# untitled.net
KiCad netlist of a schematic drawn in EAGLE
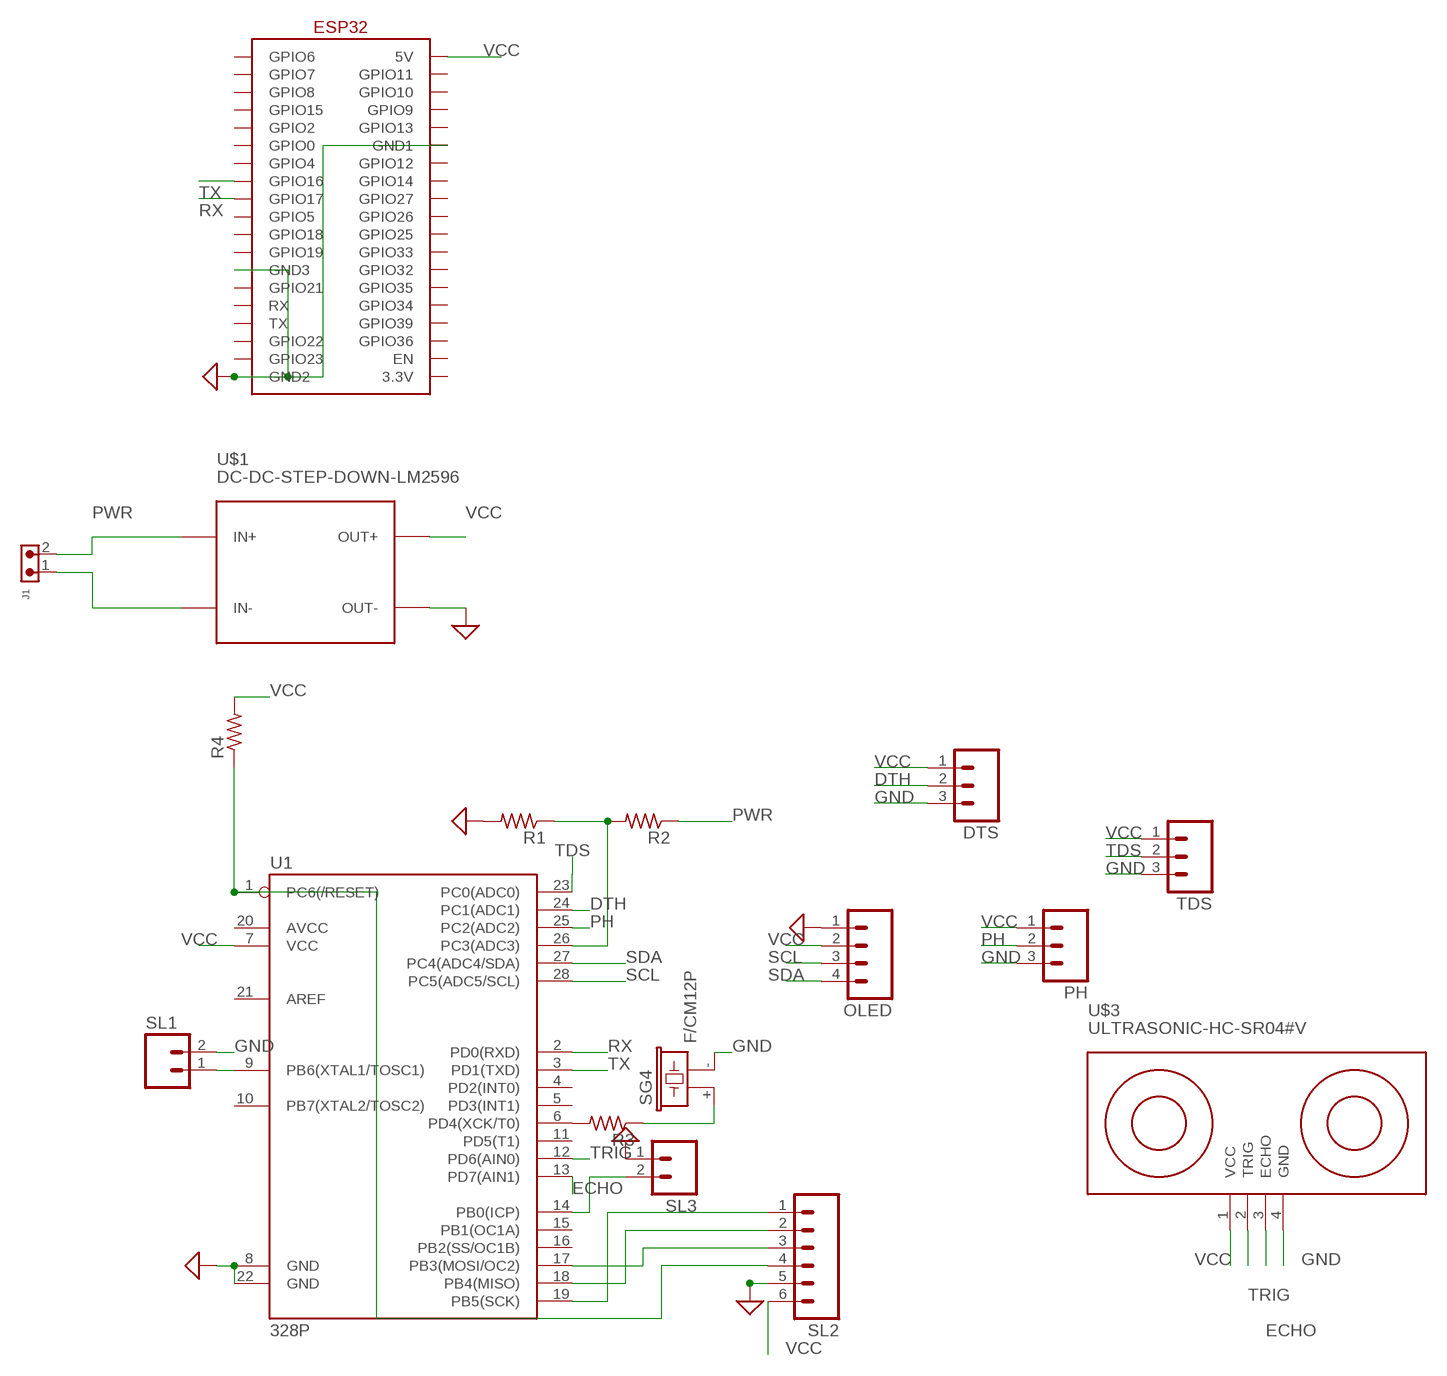
[diagram p0: schematic, sheet 1]

(export (version "E")
  (design (tool "Eeschema 10.0.6"))
  (components
    (comp (ref "DTS")
      (value "M03")
      (footprint "eagle-import:03P")
      (libsource (lib "eagle-import") (part "M03"))
    )
    (comp (ref "J1")
      (value "691305530002")
      (footprint "eagle-import:691305530002")
      (libsource (lib "eagle-import") (part "691305530002"))
    )
    (comp (ref "OLED")
      (value "M04")
      (footprint "eagle-import:04P")
      (libsource (lib "eagle-import") (part "M04"))
    )
    (comp (ref "PH")
      (value "M03")
      (footprint "eagle-import:03P")
      (libsource (lib "eagle-import") (part "M03"))
    )
    (comp (ref "R1")
      (value "R-US_0207/10")
      (footprint "eagle-import:0207_10")
      (libsource (lib "eagle-import") (part "R-US_0207/10"))
    )
    (comp (ref "R2")
      (value "R-US_0207/10")
      (footprint "eagle-import:0207_10")
      (libsource (lib "eagle-import") (part "R-US_0207/10"))
    )
    (comp (ref "R3")
      (value "R-US_0204/2V")
      (footprint "eagle-import:0204V")
      (libsource (lib "eagle-import") (part "R-US_0204/2V"))
    )
    (comp (ref "R4")
      (value "R-US_0207/10")
      (footprint "eagle-import:0207_10")
      (libsource (lib "eagle-import") (part "R-US_0207/10"))
    )
    (comp (ref "SG4")
      (value "F/CM12P")
      (footprint "eagle-import:F_CM12P")
      (libsource (lib "eagle-import") (part "F/CM12P"))
    )
    (comp (ref "SL1")
      (value "M02")
      (footprint "eagle-import:02P")
      (libsource (lib "eagle-import") (part "M02"))
    )
    (comp (ref "SL2")
      (value "M06")
      (footprint "eagle-import:06P")
      (libsource (lib "eagle-import") (part "M06"))
    )
    (comp (ref "SL3")
      (value "M02")
      (footprint "eagle-import:02P")
      (libsource (lib "eagle-import") (part "M02"))
    )
    (comp (ref "TDS")
      (value "M03")
      (footprint "eagle-import:03P")
      (libsource (lib "eagle-import") (part "M03"))
    )
    (comp (ref "U$1")
      (value "DC-DC-STEP-DOWN-LM2596")
      (footprint "eagle-import:DC-DC-STEP-DOWN-LM2596")
      (libsource (lib "eagle-import") (part "DC-DC-STEP-DOWN-LM2596"))
    )
    (comp (ref "U$2")
      (value "ESP32")
      (footprint "eagle-import:ESP32")
      (libsource (lib "eagle-import") (part "ESP32"))
    )
    (comp (ref "U$3")
      (value "ULTRASONIC-HC-SR04#V")
      (footprint "eagle-import:ULTRASONIC-HC-SR04#V")
      (libsource (lib "eagle-import") (part "ULTRASONIC-HC-SR04#V"))
    )
    (comp (ref "U1")
      (value "328P")
      (footprint "eagle-import:DIP28")
      (libsource (lib "eagle-import") (part "ATMEGA328P_PDIP"))
    )
  )
  (nets
    (net (code "1") (name "/DTH") (class "Default")
      (node (ref "DTS") (pin "2") (pinfunction "2_2") (pintype "passive"))
      (node (ref "U1") (pin "24") (pinfunction "PC1(ADC1)_24") (pintype "bidirectional"))
    )
    (net (code "2") (name "/ECHO") (class "Default")
      (node (ref "U$3") (pin "3") (pinfunction "ECHO_3") (pintype "output"))
      (node (ref "U1") (pin "13") (pinfunction "PD7(AIN1)_13") (pintype "bidirectional"))
    )
    (net (code "3") (name "/PH") (class "Default")
      (node (ref "PH") (pin "2") (pinfunction "2_2") (pintype "passive"))
      (node (ref "U1") (pin "25") (pinfunction "PC2(ADC2)_25") (pintype "bidirectional"))
    )
    (net (code "4") (name "/PWR") (class "Default")
      (node (ref "J1") (pin "2") (pinfunction "2_2") (pintype "passive"))
      (node (ref "R2") (pin "1") (pinfunction "1_1") (pintype "passive"))
      (node (ref "U$1") (pin "IN+") (pinfunction "IN+_IN+") (pintype "bidirectional"))
    )
    (net (code "5") (name "/RX") (class "Default")
      (node (ref "U$2") (pin "GPIO17") (pinfunction "GPIO17_GPIO17") (pintype "bidirectional"))
      (node (ref "U1") (pin "2") (pinfunction "PD0(RXD)_2") (pintype "bidirectional"))
    )
    (net (code "6") (name "/SCL") (class "Default")
      (node (ref "OLED") (pin "3") (pinfunction "3_3") (pintype "passive"))
      (node (ref "U1") (pin "28") (pinfunction "PC5(ADC5/SCL)_28") (pintype "bidirectional"))
    )
    (net (code "7") (name "/SDA") (class "Default")
      (node (ref "OLED") (pin "4") (pinfunction "4_4") (pintype "passive"))
      (node (ref "U1") (pin "27") (pinfunction "PC4(ADC4/SDA)_27") (pintype "bidirectional"))
    )
    (net (code "8") (name "/TDS") (class "Default")
      (node (ref "TDS") (pin "2") (pinfunction "2_2") (pintype "passive"))
      (node (ref "U1") (pin "23") (pinfunction "PC0(ADC0)_23") (pintype "bidirectional"))
    )
    (net (code "9") (name "/TRIG") (class "Default")
      (node (ref "U$3") (pin "2") (pinfunction "TRIG_2") (pintype "input"))
      (node (ref "U1") (pin "12") (pinfunction "PD6(AIN0)_12") (pintype "bidirectional"))
    )
    (net (code "10") (name "/TX") (class "Default")
      (node (ref "U$2") (pin "GPIO16") (pinfunction "GPIO16_GPIO16") (pintype "bidirectional"))
      (node (ref "U1") (pin "3") (pinfunction "PD1(TXD)_3") (pintype "bidirectional"))
    )
    (net (code "11") (name "/VCC") (class "Default")
      (node (ref "DTS") (pin "1") (pinfunction "1_1") (pintype "passive"))
      (node (ref "OLED") (pin "2") (pinfunction "2_2") (pintype "passive"))
      (node (ref "PH") (pin "1") (pinfunction "1_1") (pintype "passive"))
      (node (ref "R4") (pin "2") (pinfunction "2_2") (pintype "passive"))
      (node (ref "SL2") (pin "6") (pinfunction "6_6") (pintype "passive"))
      (node (ref "TDS") (pin "1") (pinfunction "1_1") (pintype "passive"))
      (node (ref "U$1") (pin "OUT+") (pinfunction "OUT+_OUT+") (pintype "bidirectional"))
      (node (ref "U$2") (pin "5V") (pinfunction "5V_5V") (pintype "bidirectional"))
      (node (ref "U$3") (pin "1") (pinfunction "VCC_1") (pintype "power_in"))
      (node (ref "U1") (pin "7") (pinfunction "VCC_7") (pintype "bidirectional"))
    )
    (net (code "12") (name "Net-(J1-Pad1)") (class "Default")
      (node (ref "J1") (pin "1") (pinfunction "1_1") (pintype "passive"))
      (node (ref "U$1") (pin "IN-") (pinfunction "IN-_IN-") (pintype "bidirectional"))
    )
    (net (code "13") (name "Net-(SG4-1)") (class "Default")
      (node (ref "R3") (pin "1") (pinfunction "1_1") (pintype "passive"))
      (node (ref "SG4") (pin "+") (pinfunction "1_+") (pintype "passive"))
    )
    (net (code "14") (name "Net-(U1-PB0(ICP))") (class "Default")
      (node (ref "SL3") (pin "2") (pinfunction "2_2") (pintype "passive"))
      (node (ref "U1") (pin "14") (pinfunction "PB0(ICP)_14") (pintype "bidirectional"))
    )
    (net (code "15") (name "Net-(U1-PB3(MOSI{slash}OC2))") (class "Default")
      (node (ref "SL2") (pin "3") (pinfunction "3_3") (pintype "passive"))
      (node (ref "U1") (pin "17") (pinfunction "PB3(MOSI/OC2)_17") (pintype "bidirectional"))
    )
    (net (code "16") (name "Net-(U1-PB4(MISO))") (class "Default")
      (node (ref "SL2") (pin "2") (pinfunction "2_2") (pintype "passive"))
      (node (ref "U1") (pin "18") (pinfunction "PB4(MISO)_18") (pintype "bidirectional"))
    )
    (net (code "17") (name "Net-(U1-PB5(SCK))") (class "Default")
      (node (ref "SL2") (pin "1") (pinfunction "1_1") (pintype "passive"))
      (node (ref "U1") (pin "19") (pinfunction "PB5(SCK)_19") (pintype "bidirectional"))
    )
    (net (code "18") (name "Net-(U1-PB6(XTAL1{slash}TOSC1))") (class "Default")
      (node (ref "SL1") (pin "1") (pinfunction "1_1") (pintype "passive"))
      (node (ref "U1") (pin "9") (pinfunction "PB6(XTAL1/TOSC1)_9") (pintype "bidirectional"))
    )
    (net (code "19") (name "Net-(U1-PC3(ADC3))") (class "Default")
      (node (ref "R1") (pin "1") (pinfunction "1_1") (pintype "passive"))
      (node (ref "R2") (pin "2") (pinfunction "2_2") (pintype "passive"))
      (node (ref "U1") (pin "26") (pinfunction "PC3(ADC3)_26") (pintype "bidirectional"))
    )
    (net (code "20") (name "Net-(U1-PC6({slash}RESET))") (class "Default")
      (node (ref "R4") (pin "1") (pinfunction "1_1") (pintype "passive"))
      (node (ref "SL2") (pin "4") (pinfunction "4_4") (pintype "passive"))
      (node (ref "U1") (pin "1") (pinfunction "PC6(/RESET)_1") (pintype "bidirectional"))
    )
    (net (code "21") (name "Net-(U1-PD4(XCK{slash}T0))") (class "Default")
      (node (ref "R3") (pin "2") (pinfunction "2_2") (pintype "passive"))
      (node (ref "U1") (pin "6") (pinfunction "PD4(XCK/T0)_6") (pintype "bidirectional"))
    )
    (net (code "22") (name "SUP") (class "Default")
      (node (ref "DTS") (pin "3") (pinfunction "3_3") (pintype "passive"))
      (node (ref "OLED") (pin "1") (pinfunction "1_1") (pintype "passive"))
      (node (ref "PH") (pin "3") (pinfunction "3_3") (pintype "passive"))
      (node (ref "R1") (pin "2") (pinfunction "2_2") (pintype "passive"))
      (node (ref "SG4") (pin "-") (pinfunction "2_-") (pintype "passive"))
      (node (ref "SL1") (pin "2") (pinfunction "2_2") (pintype "passive"))
      (node (ref "SL2") (pin "5") (pinfunction "5_5") (pintype "passive"))
      (node (ref "SL3") (pin "1") (pinfunction "1_1") (pintype "passive"))
      (node (ref "TDS") (pin "3") (pinfunction "3_3") (pintype "passive"))
      (node (ref "U$1") (pin "OUT-") (pinfunction "OUT-_OUT-") (pintype "bidirectional"))
      (node (ref "U$2") (pin "GND1") (pinfunction "GND1_GND1") (pintype "bidirectional"))
      (node (ref "U$2") (pin "GND2") (pinfunction "GND2_GND2") (pintype "bidirectional"))
      (node (ref "U$2") (pin "GND3") (pinfunction "GND3_GND3") (pintype "bidirectional"))
      (node (ref "U$3") (pin "4") (pinfunction "GND_4") (pintype "power_in"))
      (node (ref "U1") (pin "22") (pinfunction "GND_22") (pintype "bidirectional"))
      (node (ref "U1") (pin "8") (pinfunction "GND_8") (pintype "bidirectional"))
    )
    (net (code "23") (name "unconnected-(U$2-Pad3.3V)") (class "Default")
      (node (ref "U$2") (pin "3.3V") (pinfunction "3.3V_3.3V") (pintype "bidirectional"))
    )
    (net (code "24") (name "unconnected-(U$2-PadEN)") (class "Default")
      (node (ref "U$2") (pin "EN") (pinfunction "EN_EN") (pintype "bidirectional"))
    )
    (net (code "25") (name "unconnected-(U$2-PadGPIO0)") (class "Default")
      (node (ref "U$2") (pin "GPIO0") (pinfunction "GPIO0_GPIO0") (pintype "bidirectional"))
    )
    (net (code "26") (name "unconnected-(U$2-PadGPIO2)") (class "Default")
      (node (ref "U$2") (pin "GPIO2") (pinfunction "GPIO2_GPIO2") (pintype "bidirectional"))
    )
    (net (code "27") (name "unconnected-(U$2-PadGPIO4)") (class "Default")
      (node (ref "U$2") (pin "GPIO4") (pinfunction "GPIO4_GPIO4") (pintype "bidirectional"))
    )
    (net (code "28") (name "unconnected-(U$2-PadGPIO5)") (class "Default")
      (node (ref "U$2") (pin "GPIO5") (pinfunction "GPIO5_GPIO5") (pintype "bidirectional"))
    )
    (net (code "29") (name "unconnected-(U$2-PadGPIO6)") (class "Default")
      (node (ref "U$2") (pin "GPIO6") (pinfunction "GPIO6_GPIO6") (pintype "bidirectional"))
    )
    (net (code "30") (name "unconnected-(U$2-PadGPIO7)") (class "Default")
      (node (ref "U$2") (pin "GPIO7") (pinfunction "GPIO7_GPIO7") (pintype "bidirectional"))
    )
    (net (code "31") (name "unconnected-(U$2-PadGPIO8)") (class "Default")
      (node (ref "U$2") (pin "GPIO8") (pinfunction "GPIO8_GPIO8") (pintype "bidirectional"))
    )
    (net (code "32") (name "unconnected-(U$2-PadGPIO9)") (class "Default")
      (node (ref "U$2") (pin "GPIO9") (pinfunction "GPIO9_GPIO9") (pintype "bidirectional"))
    )
    (net (code "33") (name "unconnected-(U$2-PadGPIO10)") (class "Default")
      (node (ref "U$2") (pin "GPIO10") (pinfunction "GPIO10_GPIO10") (pintype "bidirectional"))
    )
    (net (code "34") (name "unconnected-(U$2-PadGPIO11)") (class "Default")
      (node (ref "U$2") (pin "GPIO11") (pinfunction "GPIO11_GPIO11") (pintype "bidirectional"))
    )
    (net (code "35") (name "unconnected-(U$2-PadGPIO12)") (class "Default")
      (node (ref "U$2") (pin "GPIO12") (pinfunction "GPIO12_GPIO12") (pintype "bidirectional"))
    )
    (net (code "36") (name "unconnected-(U$2-PadGPIO13)") (class "Default")
      (node (ref "U$2") (pin "GPIO13") (pinfunction "GPIO13_GPIO13") (pintype "bidirectional"))
    )
    (net (code "37") (name "unconnected-(U$2-PadGPIO14)") (class "Default")
      (node (ref "U$2") (pin "GPIO14") (pinfunction "GPIO14_GPIO14") (pintype "bidirectional"))
    )
    (net (code "38") (name "unconnected-(U$2-PadGPIO15)") (class "Default")
      (node (ref "U$2") (pin "GPIO15") (pinfunction "GPIO15_GPIO15") (pintype "bidirectional"))
    )
    (net (code "39") (name "unconnected-(U$2-PadGPIO18)") (class "Default")
      (node (ref "U$2") (pin "GPIO18") (pinfunction "GPIO18_GPIO18") (pintype "bidirectional"))
    )
    (net (code "40") (name "unconnected-(U$2-PadGPIO19)") (class "Default")
      (node (ref "U$2") (pin "GPIO19") (pinfunction "GPIO19_GPIO19") (pintype "bidirectional"))
    )
    (net (code "41") (name "unconnected-(U$2-PadGPIO21)") (class "Default")
      (node (ref "U$2") (pin "GPIO21") (pinfunction "GPIO21_GPIO21") (pintype "bidirectional"))
    )
    (net (code "42") (name "unconnected-(U$2-PadGPIO22)") (class "Default")
      (node (ref "U$2") (pin "GPIO22") (pinfunction "GPIO22_GPIO22") (pintype "bidirectional"))
    )
    (net (code "43") (name "unconnected-(U$2-PadGPIO23)") (class "Default")
      (node (ref "U$2") (pin "GPIO23") (pinfunction "GPIO23_GPIO23") (pintype "bidirectional"))
    )
    (net (code "44") (name "unconnected-(U$2-PadGPIO25)") (class "Default")
      (node (ref "U$2") (pin "GPIO25") (pinfunction "GPIO25_GPIO25") (pintype "bidirectional"))
    )
    (net (code "45") (name "unconnected-(U$2-PadGPIO26)") (class "Default")
      (node (ref "U$2") (pin "GPIO26") (pinfunction "GPIO26_GPIO26") (pintype "bidirectional"))
    )
    (net (code "46") (name "unconnected-(U$2-PadGPIO27)") (class "Default")
      (node (ref "U$2") (pin "GPIO27") (pinfunction "GPIO27_GPIO27") (pintype "bidirectional"))
    )
    (net (code "47") (name "unconnected-(U$2-PadGPIO32)") (class "Default")
      (node (ref "U$2") (pin "GPIO32") (pinfunction "GPIO32_GPIO32") (pintype "bidirectional"))
    )
    (net (code "48") (name "unconnected-(U$2-PadGPIO33)") (class "Default")
      (node (ref "U$2") (pin "GPIO33") (pinfunction "GPIO33_GPIO33") (pintype "bidirectional"))
    )
    (net (code "49") (name "unconnected-(U$2-PadGPIO34)") (class "Default")
      (node (ref "U$2") (pin "GPIO34") (pinfunction "GPIO34_GPIO34") (pintype "bidirectional"))
    )
    (net (code "50") (name "unconnected-(U$2-PadGPIO35)") (class "Default")
      (node (ref "U$2") (pin "GPIO35") (pinfunction "GPIO35_GPIO35") (pintype "bidirectional"))
    )
    (net (code "51") (name "unconnected-(U$2-PadGPIO36)") (class "Default")
      (node (ref "U$2") (pin "GPIO36") (pinfunction "GPIO36_GPIO36") (pintype "bidirectional"))
    )
    (net (code "52") (name "unconnected-(U$2-PadGPIO39)") (class "Default")
      (node (ref "U$2") (pin "GPIO39") (pinfunction "GPIO39_GPIO39") (pintype "bidirectional"))
    )
    (net (code "53") (name "unconnected-(U$2-PadRX)") (class "Default")
      (node (ref "U$2") (pin "RX") (pinfunction "RX_RX") (pintype "bidirectional"))
    )
    (net (code "54") (name "unconnected-(U$2-PadTX)") (class "Default")
      (node (ref "U$2") (pin "TX") (pinfunction "TX_TX") (pintype "bidirectional"))
    )
    (net (code "55") (name "unconnected-(U1-AREF-Pad21)") (class "Default")
      (node (ref "U1") (pin "21") (pinfunction "AREF_21") (pintype "bidirectional"))
    )
    (net (code "56") (name "unconnected-(U1-AVCC-Pad20)") (class "Default")
      (node (ref "U1") (pin "20") (pinfunction "AVCC_20") (pintype "bidirectional"))
    )
    (net (code "57") (name "unconnected-(U1-PB1(OC1A)-Pad15)") (class "Default")
      (node (ref "U1") (pin "15") (pinfunction "PB1(OC1A)_15") (pintype "bidirectional"))
    )
    (net (code "58") (name "unconnected-(U1-PB2(SS{slash}OC1B)-Pad16)") (class "Default")
      (node (ref "U1") (pin "16") (pinfunction "PB2(SS/OC1B)_16") (pintype "bidirectional"))
    )
    (net (code "59") (name "unconnected-(U1-PB7(XTAL2{slash}TOSC2)-Pad10)") (class "Default")
      (node (ref "U1") (pin "10") (pinfunction "PB7(XTAL2/TOSC2)_10") (pintype "bidirectional"))
    )
    (net (code "60") (name "unconnected-(U1-PD2(INT0)-Pad4)") (class "Default")
      (node (ref "U1") (pin "4") (pinfunction "PD2(INT0)_4") (pintype "bidirectional"))
    )
    (net (code "61") (name "unconnected-(U1-PD3(INT1)-Pad5)") (class "Default")
      (node (ref "U1") (pin "5") (pinfunction "PD3(INT1)_5") (pintype "bidirectional"))
    )
    (net (code "62") (name "unconnected-(U1-PD5(T1)-Pad11)") (class "Default")
      (node (ref "U1") (pin "11") (pinfunction "PD5(T1)_11") (pintype "bidirectional"))
    )
  )
)
